# Sheet-nilm1.net
KiCad netlist of a schematic drawn in Altium Designer
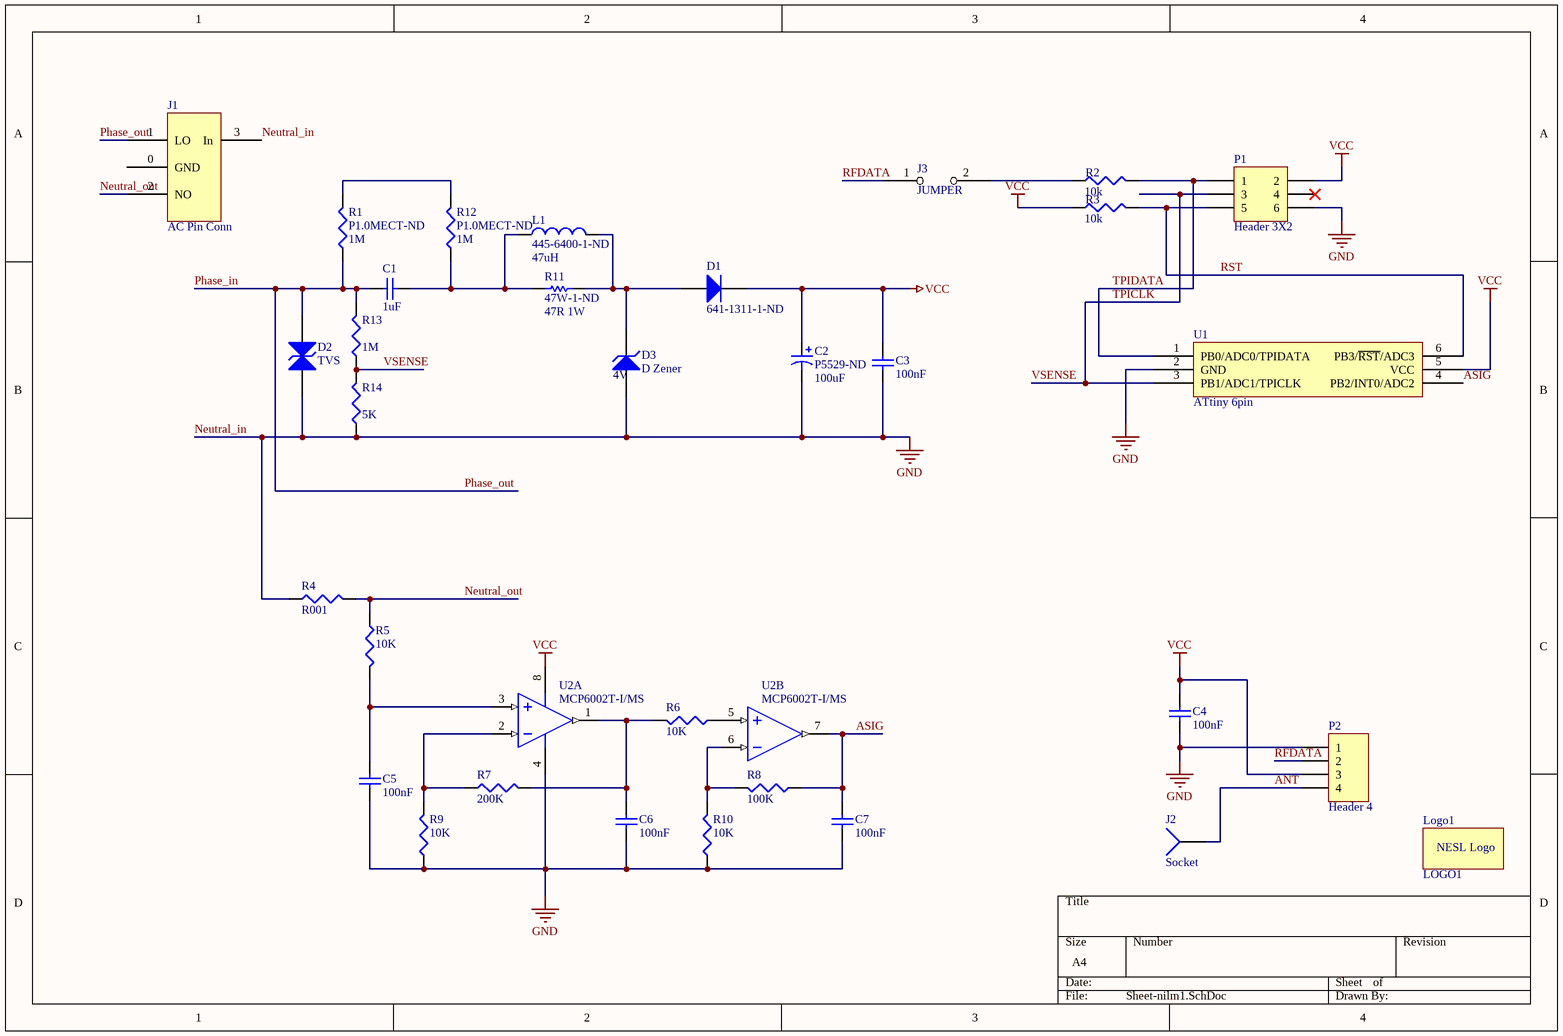
[diagram p0: Sheet-nilm1.SchDoc]

(export (version "E")
  (design (tool "Eeschema 10.0.6"))
  (components
    (comp (ref "C1")
      (value "1uF")
      (footprint "CAP-22.5mm")
      (description "Capacitor")
      (fields (field (name "PUBLISHER") "Altium Limited"))
      (libsource (lib "Miscellaneous Devices") (part "Cap"))
    )
    (comp (ref "C2")
      (value "P5529-ND")
      (footprint "CAPPR2-5x6.8")
      (description "Polarized Capacitor (Surface Mount)")
      (fields (field (name "ALTIUM_VALUE") "100uF") (field (name "PUBLISHER") "Altium Limited"))
      (libsource (lib "Miscellaneous Devices") (part "Cap Pol3"))
    )
    (comp (ref "C3")
      (value "100nF")
      (footprint "CAPC1608L")
      (description "Capacitor (Semiconductor SIM Model)")
      (fields (field (name "PUBLISHER") "Altium Limited"))
      (libsource (lib "Miscellaneous Devices") (part "Cap Semi"))
    )
    (comp (ref "C4")
      (value "100nF")
      (footprint "CAPC1608L")
      (description "Capacitor (Semiconductor SIM Model)")
      (fields (field (name "PUBLISHER") "Altium Limited"))
      (libsource (lib "Miscellaneous Devices") (part "Cap Semi"))
    )
    (comp (ref "C5")
      (value "100nF")
      (footprint "CAPC1608L")
      (description "Capacitor (Semiconductor SIM Model)")
      (fields (field (name "PUBLISHER") "Altium Limited"))
      (libsource (lib "Miscellaneous Devices") (part "Cap Semi"))
    )
    (comp (ref "C6")
      (value "100nF")
      (footprint "CAPC1608L")
      (description "Capacitor (Semiconductor SIM Model)")
      (fields (field (name "PUBLISHER") "Altium Limited"))
      (libsource (lib "Miscellaneous Devices") (part "Cap Semi"))
    )
    (comp (ref "C7")
      (value "100nF")
      (footprint "CAPC1608L")
      (description "Capacitor (Semiconductor SIM Model)")
      (fields (field (name "PUBLISHER") "Altium Limited"))
      (libsource (lib "Miscellaneous Devices") (part "Cap Semi"))
    )
    (comp (ref "D1")
      (value "641-1311-1-ND")
      (footprint "DIO9.2-4.1x2.5")
      (description "Default Diode")
      (fields (field (name "PUBLISHER") "Altium Limited"))
      (libsource (lib "Miscellaneous Devices") (part "Diode"))
    )
    (comp (ref "D2")
      (value "TVS")
      (footprint "CD4532-1812")
      (fields (field (name "PUBLISHER") "Altium Limited"))
      (libsource (lib "2011_Tianji_2") (part "TVS"))
    )
    (comp (ref "D3")
      (value "D Zener")
      (footprint "SOD123/X.85")
      (description "MMSZ5229BFSCT-ND")
      (fields (field (name "ALTIUM_VALUE") "4V") (field (name "PUBLISHER") "Altium Limited"))
      (libsource (lib "Miscellaneous Devices") (part "D Zener"))
    )
    (comp (ref "J1")
      (value "AC Pin Conn")
      (footprint "AC_PLUG")
      (libsource (lib "2011_Tianji_2") (part "AC_Plug"))
    )
    (comp (ref "J2")
      (value "Socket")
      (footprint "PIN1")
      (fields (field (name "PUBLISHER") "Altium Limited"))
      (libsource (lib "Miscellaneous Connectors") (part "Socket"))
    )
    (comp (ref "J3") (value "JUMPER") (footprint "HDR1X2") (libsource (lib "FriedParts") (part "JUMPER")))
    (comp (ref "L1")
      (value "445-6400-1-ND")
      (footprint "INDC2012L")
      (description "Inductor")
      (fields (field (name "ALTIUM_VALUE") "47uH") (field (name "PUBLISHER") "Altium Limited"))
      (libsource (lib "Miscellaneous Devices") (part "Inductor"))
    )
    (comp (ref "Logo1")
      (value "LOGO1")
      (footprint "NESL_logo")
      (description "NESL LOGO COPPER SMALL")
      (libsource (lib "FriedParts") (part "NESL logo"))
    )
    (comp (ref "P1")
      (value "Header 3X2")
      (footprint "6-pin 2mm")
      (description "Header, 3-Pin, Dual row")
      (fields (field (name "PUBLISHER") "Altium Limited"))
      (libsource (lib "Miscellaneous Connectors") (part "Header 3X2"))
    )
    (comp (ref "P2")
      (value "Header 4")
      (footprint "HDR1X4")
      (description "Header, 4-Pin")
      (fields (field (name "PUBLISHER") "Altium Limited"))
      (libsource (lib "Miscellaneous Connectors") (part "Header 4"))
    )
    (comp (ref "R1")
      (value "P1.0MECT-ND")
      (footprint "RESC3216L")
      (description "Resistor")
      (fields (field (name "ALTIUM_VALUE") "1M") (field (name "PUBLISHER") "Altium Limited"))
      (libsource (lib "Miscellaneous Devices") (part "Res3"))
    )
    (comp (ref "R2")
      (value "10k")
      (footprint "RESC1608L")
      (description "Resistor")
      (fields (field (name "PUBLISHER") "Altium Limited"))
      (libsource (lib "Miscellaneous Devices") (part "Res3"))
    )
    (comp (ref "R3")
      (value "10k")
      (footprint "RESC1608L")
      (description "Resistor")
      (fields (field (name "PUBLISHER") "Altium Limited"))
      (libsource (lib "Miscellaneous Devices") (part "Res3"))
    )
    (comp (ref "R4")
      (value "R001")
      (footprint "RESC6332L")
      (description "Resistor")
      (fields (field (name "PUBLISHER") "Altium Limited"))
      (libsource (lib "Miscellaneous Devices") (part "Res3"))
    )
    (comp (ref "R5")
      (value "10K")
      (footprint "RESC1608L")
      (description "Resistor")
      (fields (field (name "PUBLISHER") "Altium Limited"))
      (libsource (lib "Miscellaneous Devices") (part "Res3"))
    )
    (comp (ref "R6")
      (value "10K")
      (footprint "RESC1608L")
      (description "Resistor")
      (fields (field (name "PUBLISHER") "Altium Limited"))
      (libsource (lib "Miscellaneous Devices") (part "Res3"))
    )
    (comp (ref "R7")
      (value "200K")
      (footprint "RESC1608L")
      (description "Resistor")
      (fields (field (name "PUBLISHER") "Altium Limited"))
      (libsource (lib "Miscellaneous Devices") (part "Res3"))
    )
    (comp (ref "R8")
      (value "100K")
      (footprint "RESC1608L")
      (description "Resistor")
      (fields (field (name "PUBLISHER") "Altium Limited"))
      (libsource (lib "Miscellaneous Devices") (part "Res3"))
    )
    (comp (ref "R9")
      (value "10K")
      (footprint "RESC1608L")
      (description "Resistor")
      (fields (field (name "PUBLISHER") "Altium Limited"))
      (libsource (lib "Miscellaneous Devices") (part "Res3"))
    )
    (comp (ref "R10")
      (value "10K")
      (footprint "RESC1608L")
      (description "Resistor")
      (fields (field (name "PUBLISHER") "Altium Limited"))
      (libsource (lib "Miscellaneous Devices") (part "Res3"))
    )
    (comp (ref "R11")
      (value "47W-1-ND")
      (footprint "RES45x115VERT")
      (description "Resistor")
      (fields (field (name "ALTIUM_VALUE") "47R 1W") (field (name "PUBLISHER") "Altium Limited"))
      (libsource (lib "Miscellaneous Devices") (part "Res1"))
    )
    (comp (ref "R12")
      (value "P1.0MECT-ND")
      (footprint "RESC3216L")
      (description "Resistor")
      (fields (field (name "ALTIUM_VALUE") "1M") (field (name "PUBLISHER") "Altium Limited"))
      (libsource (lib "Miscellaneous Devices") (part "Res3"))
    )
    (comp (ref "R13")
      (value "1M")
      (footprint "RESC3216L")
      (description "Resistor")
      (fields (field (name "PUBLISHER") "Altium Limited"))
      (libsource (lib "Miscellaneous Devices") (part "Res3"))
    )
    (comp (ref "R14")
      (value "5K")
      (footprint "RESC3216L")
      (description "Resistor")
      (fields (field (name "PUBLISHER") "Altium Limited"))
      (libsource (lib "Miscellaneous Devices") (part "Res3"))
    )
    (comp (ref "U1")
      (value "ATtiny 6pin")
      (footprint "SOT23-6M")
      (description "ATtiny4/5/9/10")
      (libsource (lib "2011_Tianji_2") (part "ATtiny4/5/9/10"))
    )
    (comp (ref "U2")
      (value "MCP6002T-I/MS")
      (footprint "MSOP65P-8N")
      (description "mcp6002 series 6 v 1 mhz smt low")
      (libsource (lib "FriedParts") (part "MCP6002"))
    )
  )
  (nets
    (net (code "1") (name "/ANT") (class "Default")
      (node (ref "J2") (pin "1") (pinfunction "1_1") (pintype "passive"))
      (node (ref "P2") (pin "4") (pinfunction "4_4") (pintype "passive"))
    )
    (net (code "2") (name "/ASIG") (class "Default")
      (node (ref "C7") (pin "2") (pinfunction "2_2") (pintype "passive"))
      (node (ref "R8") (pin "1") (pinfunction "1_1") (pintype "passive"))
      (node (ref "U1") (pin "4") (pinfunction "PB2/INT0/ADC2_4") (pintype "passive"))
      (node (ref "U2") (pin "7") (pinfunction "OUT_7") (pintype "output"))
    )
    (net (code "3") (name "/Neutral_out") (class "Default")
      (node (ref "J1") (pin "2") (pinfunction "NO_2") (pintype "passive"))
      (node (ref "R4") (pin "2") (pinfunction "2_2") (pintype "passive"))
      (node (ref "R5") (pin "1") (pinfunction "1_1") (pintype "passive"))
    )
    (net (code "4") (name "/Phase_in") (class "Default")
      (node (ref "C1") (pin "1") (pinfunction "1_1") (pintype "passive"))
      (node (ref "D2") (pin "2") (pinfunction "K_2") (pintype "passive"))
      (node (ref "J1") (pin "1") (pinfunction "LO_1") (pintype "passive"))
      (node (ref "R1") (pin "1") (pinfunction "1_1") (pintype "passive"))
      (node (ref "R13") (pin "2") (pinfunction "2_2") (pintype "passive"))
    )
    (net (code "5") (name "/RFDATA") (class "Default")
      (node (ref "J3") (pin "1") (pinfunction "1_1") (pintype "passive"))
      (node (ref "P2") (pin "2") (pinfunction "2_2") (pintype "passive"))
    )
    (net (code "6") (name "/RST") (class "Default")
      (node (ref "P1") (pin "5") (pinfunction "5_5") (pintype "passive"))
      (node (ref "R3") (pin "2") (pinfunction "2_2") (pintype "passive"))
      (node (ref "U1") (pin "6") (pinfunction "PB3/~{RST}/ADC3_6") (pintype "passive"))
    )
    (net (code "7") (name "/TPICLK") (class "Default")
      (node (ref "P1") (pin "3") (pinfunction "3_3") (pintype "passive"))
      (node (ref "R13") (pin "1") (pinfunction "1_1") (pintype "passive"))
      (node (ref "R14") (pin "2") (pinfunction "2_2") (pintype "passive"))
      (node (ref "U1") (pin "3") (pinfunction "PB1/ADC1/TPICLK_3") (pintype "passive"))
    )
    (net (code "8") (name "/TPIDATA") (class "Default")
      (node (ref "P1") (pin "1") (pinfunction "1_1") (pintype "passive"))
      (node (ref "R2") (pin "2") (pinfunction "2_2") (pintype "passive"))
      (node (ref "U1") (pin "1") (pinfunction "PB0/ADC0/TPIDATA_1") (pintype "passive"))
    )
    (net (code "9") (name "GND") (class "Default")
      (node (ref "C2") (pin "2") (pinfunction "2_2") (pintype "passive"))
      (node (ref "C3") (pin "1") (pinfunction "1_1") (pintype "passive"))
      (node (ref "C4") (pin "1") (pinfunction "1_1") (pintype "passive"))
      (node (ref "C5") (pin "1") (pinfunction "1_1") (pintype "passive"))
      (node (ref "C6") (pin "1") (pinfunction "1_1") (pintype "passive"))
      (node (ref "C7") (pin "1") (pinfunction "1_1") (pintype "passive"))
      (node (ref "D2") (pin "1") (pinfunction "A_1") (pintype "passive"))
      (node (ref "D3") (pin "1") (pinfunction "A_1") (pintype "passive"))
      (node (ref "J1") (pin "3") (pinfunction "In_3") (pintype "passive"))
      (node (ref "P1") (pin "6") (pinfunction "6_6") (pintype "passive"))
      (node (ref "P2") (pin "1") (pinfunction "1_1") (pintype "passive"))
      (node (ref "R10") (pin "1") (pinfunction "1_1") (pintype "passive"))
      (node (ref "R14") (pin "1") (pinfunction "1_1") (pintype "passive"))
      (node (ref "R4") (pin "1") (pinfunction "1_1") (pintype "passive"))
      (node (ref "R9") (pin "1") (pinfunction "1_1") (pintype "passive"))
      (node (ref "U1") (pin "2") (pinfunction "GND_2") (pintype "passive"))
      (node (ref "U2") (pin "4") (pinfunction "V-_4") (pintype "power_in"))
    )
    (net (code "10") (name "Net-(C1-Pad2)") (class "Default")
      (node (ref "C1") (pin "2") (pinfunction "2_2") (pintype "passive"))
      (node (ref "L1") (pin "1") (pinfunction "1_1") (pintype "passive"))
      (node (ref "R11") (pin "1") (pinfunction "1_1") (pintype "passive"))
      (node (ref "R12") (pin "1") (pinfunction "1_1") (pintype "passive"))
    )
    (net (code "11") (name "Net-(D1-A)") (class "Default")
      (node (ref "D1") (pin "1") (pinfunction "A_1") (pintype "passive"))
      (node (ref "D3") (pin "2") (pinfunction "K_2") (pintype "passive"))
      (node (ref "L1") (pin "2") (pinfunction "2_2") (pintype "passive"))
      (node (ref "R11") (pin "2") (pinfunction "2_2") (pintype "passive"))
    )
    (net (code "12") (name "Net-(J3-Pad2)") (class "Default")
      (node (ref "J3") (pin "2") (pinfunction "2_2") (pintype "passive"))
      (node (ref "R2") (pin "1") (pinfunction "1_1") (pintype "passive"))
    )
    (net (code "13") (name "Net-(R1-Pad2)") (class "Default")
      (node (ref "R1") (pin "2") (pinfunction "2_2") (pintype "passive"))
      (node (ref "R12") (pin "2") (pinfunction "2_2") (pintype "passive"))
    )
    (net (code "14") (name "Net-(U2A-IN+)") (class "Default")
      (node (ref "C5") (pin "2") (pinfunction "2_2") (pintype "passive"))
      (node (ref "R5") (pin "2") (pinfunction "2_2") (pintype "passive"))
      (node (ref "U2") (pin "3") (pinfunction "IN+_3") (pintype "input"))
    )
    (net (code "15") (name "Net-(U2A-IN-)") (class "Default")
      (node (ref "R7") (pin "1") (pinfunction "1_1") (pintype "passive"))
      (node (ref "R9") (pin "2") (pinfunction "2_2") (pintype "passive"))
      (node (ref "U2") (pin "2") (pinfunction "IN-_2") (pintype "input"))
    )
    (net (code "16") (name "Net-(U2A-OUT)") (class "Default")
      (node (ref "C6") (pin "2") (pinfunction "2_2") (pintype "passive"))
      (node (ref "R6") (pin "2") (pinfunction "2_2") (pintype "passive"))
      (node (ref "R7") (pin "2") (pinfunction "2_2") (pintype "passive"))
      (node (ref "U2") (pin "1") (pinfunction "OUT_1") (pintype "output"))
    )
    (net (code "17") (name "Net-(U2B-IN+)") (class "Default")
      (node (ref "R6") (pin "1") (pinfunction "1_1") (pintype "passive"))
      (node (ref "U2") (pin "5") (pinfunction "IN+_5") (pintype "input"))
    )
    (net (code "18") (name "Net-(U2B-IN-)") (class "Default")
      (node (ref "R10") (pin "2") (pinfunction "2_2") (pintype "passive"))
      (node (ref "R8") (pin "2") (pinfunction "2_2") (pintype "passive"))
      (node (ref "U2") (pin "6") (pinfunction "IN-_6") (pintype "input"))
    )
    (net (code "19") (name "VCC") (class "Default")
      (node (ref "C2") (pin "1") (pinfunction "1_1") (pintype "passive"))
      (node (ref "C3") (pin "2") (pinfunction "2_2") (pintype "passive"))
      (node (ref "C4") (pin "2") (pinfunction "2_2") (pintype "passive"))
      (node (ref "D1") (pin "2") (pinfunction "K_2") (pintype "passive"))
      (node (ref "P1") (pin "2") (pinfunction "2_2") (pintype "passive"))
      (node (ref "P2") (pin "3") (pinfunction "3_3") (pintype "passive"))
      (node (ref "R3") (pin "1") (pinfunction "1_1") (pintype "passive"))
      (node (ref "U1") (pin "5") (pinfunction "VCC_5") (pintype "passive"))
      (node (ref "U2") (pin "8") (pinfunction "V+_8") (pintype "power_in"))
    )
    (net (code "20") (name "unconnected-(J1-GND-Pad0)") (class "Default")
      (node (ref "J1") (pin "0") (pinfunction "GND_0") (pintype "passive"))
    )
    (net (code "21") (name "unconnected-(P1-Pad4)") (class "Default")
      (node (ref "P1") (pin "4") (pinfunction "4_4") (pintype "passive+no_connect"))
    )
  )
)
